# ep_project.net
KiCad netlist of a schematic drawn in EAGLE
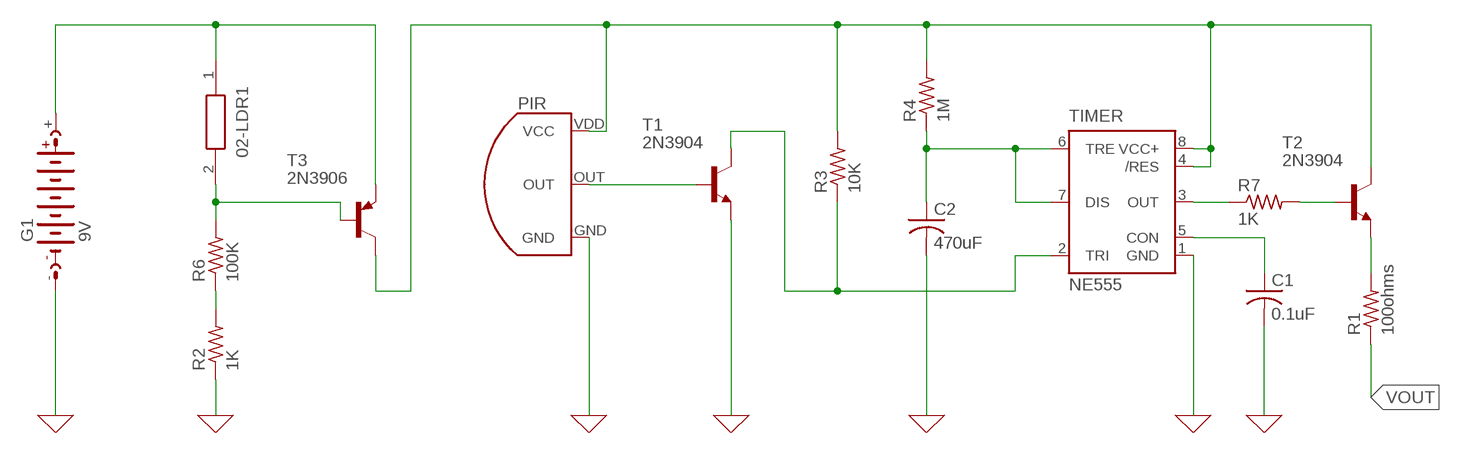
[diagram p0: schematic, sheet 1]

(export (version "E")
  (design (tool "Eeschema 10.0.6"))
  (components
    (comp (ref "C1")
      (value "0.1uF")
      (footprint "eagle-import:C025-024X044")
      (fields (field (name "MF") "KEMET") (field (name "MPN") "C0603C104M4RACTU."))
      (libsource (lib "eagle-import") (part "C-US025-024X044"))
    )
    (comp (ref "C2")
      (value "470uF")
      (footprint "eagle-import:C025-024X044")
      (fields (field (name "MF") "ILLINOIS CAPACITOR") (field (name "MPN") "477CKE016M ."))
      (libsource (lib "eagle-import") (part "C-US025-024X044"))
    )
    (comp (ref "G1")
      (value "9V")
      (footprint "eagle-import:AB9V")
      (fields (field (name "MF") "KEYSTONE") (field (name "MPN") "1294"))
      (libsource (lib "eagle-import") (part "AB9V"))
    )
    (comp (ref "PIR")
      (value "EKMC4607112k")
      (footprint "eagle-import:TO-3")
      (fields (field (name "MF") "PANASONIC") (field (name "MPN") "EKMC1603111"))
      (libsource (lib "eagle-import") (part "PIR_EKM4607112K"))
    )
    (comp (ref "R1")
      (value "100ohms")
      (footprint "eagle-import:M0805")
      (fields (field (name "MF") "MULTICOMP PRO") (field (name "MPN") "MCMF0W4FF1000A50"))
      (libsource (lib "eagle-import") (part "R-US_M0805"))
    )
    (comp (ref "R2")
      (value "1K")
      (footprint "eagle-import:M0805")
      (fields (field (name "MF") "NEOHM - TE CONNECTIVITY") (field (name "MPN") "YR1B1K0CC"))
      (libsource (lib "eagle-import") (part "R-US_M0805"))
    )
    (comp (ref "R3")
      (value "10K")
      (footprint "eagle-import:M0805")
      (fields (field (name "MF") "NEOHM - TE CONNECTIVITY") (field (name "MPN") "YR1B10KCC"))
      (libsource (lib "eagle-import") (part "R-US_M0805"))
    )
    (comp (ref "R4")
      (value "1M")
      (footprint "eagle-import:M0805")
      (fields (field (name "MF") "VISHAY") (field (name "MPN") "MBB02070C1004FC100"))
      (libsource (lib "eagle-import") (part "R-US_M0805"))
    )
    (comp (ref "R5")
      (value "02-LDR1")
      (footprint "eagle-import:02LDR1")
      (fields (field (name "MF") "EXCELITAS TECH") (field (name "MPN") "VT935G"))
      (libsource (lib "eagle-import") (part "02-LDR1"))
    )
    (comp (ref "R6")
      (value "100K")
      (footprint "eagle-import:M0805")
      (fields (field (name "MF") "MULTICOMP PRO") (field (name "MPN") "MCMF0W2FF1003A10"))
      (libsource (lib "eagle-import") (part "R-US_M0805"))
    )
    (comp (ref "R7")
      (value "1K")
      (footprint "eagle-import:M0805")
      (fields (field (name "MF") "NEOHM - TE CONNECTIVITY") (field (name "MPN") "YR1B1K0CC"))
      (libsource (lib "eagle-import") (part "R-US_M0805"))
    )
    (comp (ref "T1")
      (value "2N3904")
      (footprint "eagle-import:TO92")
      (fields (field (name "MF") "ONSEMI") (field (name "MPN") "2N3904TFR."))
      (libsource (lib "eagle-import") (part "2N3904"))
    )
    (comp (ref "T2")
      (value "2N3904")
      (footprint "eagle-import:TO92")
      (fields (field (name "MF") "ONSEMI") (field (name "MPN") "2N3904TFR."))
      (libsource (lib "eagle-import") (part "2N3904"))
    )
    (comp (ref "T3")
      (value "2N3906")
      (footprint "eagle-import:TO92")
      (fields (field (name "MF") "MULTICOMP PRO"))
      (libsource (lib "eagle-import") (part "2N3906"))
    )
    (comp (ref "TIMER")
      (value "NE555")
      (footprint "eagle-import:DIL-08")
      (fields
        (field (name "MF") "Arrow Electronics")
        (field (name "MPN") "NE555N")
        (field (name "MF_1") "STMICROELECTRONICS")
      )
      (libsource (lib "eagle-import") (part "NE555"))
    )
  )
  (nets
    (net (code "1") (name "GND") (class "Default")
      (node (ref "C1") (pin "2") (pinfunction "2_2") (pintype "passive"))
      (node (ref "C2") (pin "2") (pinfunction "2_2") (pintype "passive"))
      (node (ref "G1") (pin "-") (pinfunction "-_-") (pintype "passive"))
      (node (ref "PIR") (pin "GND") (pinfunction "GND_GND") (pintype "bidirectional"))
      (node (ref "R2") (pin "1") (pinfunction "1_1") (pintype "passive"))
      (node (ref "T1") (pin "3") (pinfunction "E_3") (pintype "passive"))
      (node (ref "TIMER") (pin "1") (pinfunction "GND_1") (pintype "power_in"))
    )
    (net (code "2") (name "Net-(PIR-VCC)") (class "Default")
      (node (ref "PIR") (pin "VDD") (pinfunction "VCC_VDD") (pintype "bidirectional"))
      (node (ref "R3") (pin "2") (pinfunction "2_2") (pintype "passive"))
      (node (ref "R4") (pin "2") (pinfunction "2_2") (pintype "passive"))
      (node (ref "T2") (pin "1") (pinfunction "C_1") (pintype "passive"))
      (node (ref "T3") (pin "1") (pinfunction "C_1") (pintype "passive"))
      (node (ref "TIMER") (pin "4") (pinfunction "/RES_4") (pintype "input"))
      (node (ref "TIMER") (pin "8") (pinfunction "VCC+_8") (pintype "power_in"))
    )
    (net (code "3") (name "Net-(R2-Pad2)") (class "Default")
      (node (ref "R2") (pin "2") (pinfunction "2_2") (pintype "passive"))
      (node (ref "R6") (pin "1") (pinfunction "1_1") (pintype "passive"))
    )
    (net (code "4") (name "Net-(T1-B)") (class "Default")
      (node (ref "PIR") (pin "OUT") (pinfunction "OUT_OUT") (pintype "bidirectional"))
      (node (ref "T1") (pin "2") (pinfunction "B_2") (pintype "passive"))
    )
    (net (code "5") (name "Net-(T1-C)") (class "Default")
      (node (ref "R3") (pin "1") (pinfunction "1_1") (pintype "passive"))
      (node (ref "T1") (pin "1") (pinfunction "C_1") (pintype "passive"))
      (node (ref "TIMER") (pin "2") (pinfunction "TRI_2") (pintype "input"))
    )
    (net (code "6") (name "Net-(T2-B)") (class "Default")
      (node (ref "R7") (pin "2") (pinfunction "2_2") (pintype "passive"))
      (node (ref "T2") (pin "2") (pinfunction "B_2") (pintype "passive"))
    )
    (net (code "7") (name "Net-(T2-E)") (class "Default")
      (node (ref "R1") (pin "2") (pinfunction "2_2") (pintype "passive"))
      (node (ref "T2") (pin "3") (pinfunction "E_3") (pintype "passive"))
    )
    (net (code "8") (name "Net-(T3-B)") (class "Default")
      (node (ref "R5") (pin "2") (pinfunction "2_2") (pintype "bidirectional"))
      (node (ref "R6") (pin "2") (pinfunction "2_2") (pintype "passive"))
      (node (ref "T3") (pin "2") (pinfunction "B_2") (pintype "passive"))
    )
    (net (code "9") (name "Net-(T3-E)") (class "Default")
      (node (ref "G1") (pin "+") (pinfunction "+_+") (pintype "passive"))
      (node (ref "R5") (pin "1") (pinfunction "1_1") (pintype "bidirectional"))
      (node (ref "T3") (pin "3") (pinfunction "E_3") (pintype "passive"))
    )
    (net (code "10") (name "Net-(TIMER-CON)") (class "Default")
      (node (ref "C1") (pin "1") (pinfunction "1_1") (pintype "passive"))
      (node (ref "TIMER") (pin "5") (pinfunction "CON_5") (pintype "input"))
    )
    (net (code "11") (name "Net-(TIMER-DIS)") (class "Default")
      (node (ref "C2") (pin "1") (pinfunction "1_1") (pintype "passive"))
      (node (ref "R4") (pin "1") (pinfunction "1_1") (pintype "passive"))
      (node (ref "TIMER") (pin "6") (pinfunction "TRE_6") (pintype "input"))
      (node (ref "TIMER") (pin "7") (pinfunction "DIS_7") (pintype "input"))
    )
    (net (code "12") (name "Net-(TIMER-OUT)") (class "Default")
      (node (ref "R7") (pin "1") (pinfunction "1_1") (pintype "passive"))
      (node (ref "TIMER") (pin "3") (pinfunction "OUT_3") (pintype "output"))
    )
    (net (code "13") (name "VOUT") (class "Default")
      (node (ref "R1") (pin "1") (pinfunction "1_1") (pintype "passive"))
    )
  )
)
